# module.net
KiCad netlist of a schematic drawn in Altium Designer
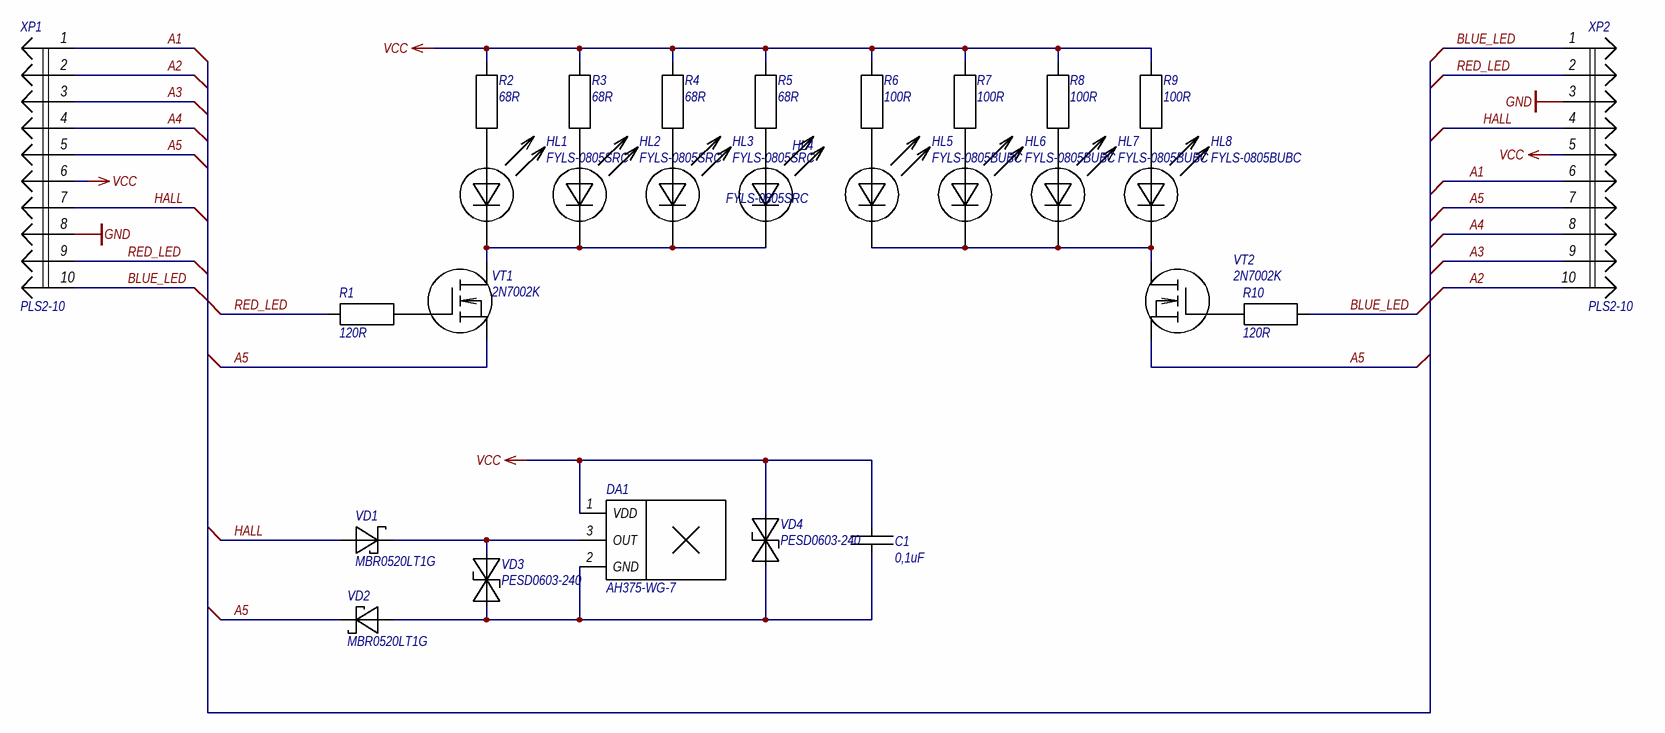
[diagram p0: module.SchDoc]

(export (version "E")
  (design (tool "Eeschema 10.0.6"))
  (components
    (comp (ref "C1")
      (value "0,1uF")
      (footprint "C0805C")
      (description "CC0805KKX7R0BB104, 0805 X7R  0,1 uF 100V")
      (fields (field (name "PART NUMBER") "CC0805KKX7R0BB104") (field (name "MANUFACTURER") "Yageo"))
      (libsource (lib "lib") (part "Cap"))
    )
    (comp (ref "DA1")
      (value "AH375-WG-7")
      (footprint "SOT23-3(1-3-2)")
      (description "SINGLE PHASE HALL EFFECT LATCH")
      (fields (field (name "MANUFACTURER") "Diodes Incorporated"))
      (libsource (lib "lib") (part "AH375"))
    )
    (comp (ref "HL1")
      (value "FYLS-0805SRC")
      (footprint "LED0805")
      (description "SMD 0805 Red 20mA 15mcd")
      (fields (field (name "MANUFACTURER") "Foryard") (field (name "VOLTAGE") "1,7V"))
      (libsource (lib "lib") (part "LED"))
    )
    (comp (ref "HL2")
      (value "FYLS-0805SRC")
      (footprint "LED0805")
      (description "SMD 0805 Red 20mA 15mcd")
      (fields (field (name "MANUFACTURER") "Foryard") (field (name "VOLTAGE") "1,7V"))
      (libsource (lib "lib") (part "LED"))
    )
    (comp (ref "HL3")
      (value "FYLS-0805SRC")
      (footprint "LED0805")
      (description "SMD 0805 Red 20mA 15mcd")
      (fields (field (name "MANUFACTURER") "Foryard") (field (name "VOLTAGE") "1,7V"))
      (libsource (lib "lib") (part "LED"))
    )
    (comp (ref "HL4")
      (value "FYLS-0805SRC")
      (footprint "LED0805")
      (description "SMD 0805 Red 20mA 15mcd")
      (fields (field (name "MANUFACTURER") "Foryard") (field (name "VOLTAGE") "1,7V"))
      (libsource (lib "lib") (part "LED"))
    )
    (comp (ref "HL5")
      (value "FYLS-0805BUBC")
      (footprint "LED0805")
      (description "SMD 0805 Blue 20mA 120mcd")
      (fields (field (name "MANUFACTURER") "Foryard") (field (name "VOLTAGE") "3.2V"))
      (libsource (lib "lib") (part "LED"))
    )
    (comp (ref "HL6")
      (value "FYLS-0805BUBC")
      (footprint "LED0805")
      (description "SMD 0805 Blue 20mA 120mcd")
      (fields (field (name "MANUFACTURER") "Foryard") (field (name "VOLTAGE") "3.2V"))
      (libsource (lib "lib") (part "LED"))
    )
    (comp (ref "HL7")
      (value "FYLS-0805BUBC")
      (footprint "LED0805")
      (description "SMD 0805 Blue 20mA 120mcd")
      (fields (field (name "MANUFACTURER") "Foryard") (field (name "VOLTAGE") "3.2V"))
      (libsource (lib "lib") (part "LED"))
    )
    (comp (ref "HL8")
      (value "FYLS-0805BUBC")
      (footprint "LED0805")
      (description "SMD 0805 Blue 20mA 120mcd")
      (fields (field (name "MANUFACTURER") "Foryard") (field (name "VOLTAGE") "3.2V"))
      (libsource (lib "lib") (part "LED"))
    )
    (comp (ref "R1")
      (value "120R")
      (footprint "C0603R")
      (description "RC0603FR-07120RL, 1% 120R")
      (fields (field (name "PART NUMBER") "RC0603FR-07120RL") (field (name "MANUFACTURER") "Yageo"))
      (libsource (lib "lib") (part "res"))
    )
    (comp (ref "R2")
      (value "68R")
      (footprint "C0805R")
      (description "RC0805FR-0768RL, 1% 68R")
      (fields (field (name "PART NUMBER") "RC0805FR-0768RL") (field (name "MANUFACTURER") "Yageo"))
      (libsource (lib "lib") (part "res"))
    )
    (comp (ref "R3")
      (value "68R")
      (footprint "C0805R")
      (description "RC0805FR-0768RL, 1% 68R")
      (fields (field (name "PART NUMBER") "RC0805FR-0768RL") (field (name "MANUFACTURER") "Yageo"))
      (libsource (lib "lib") (part "res"))
    )
    (comp (ref "R4")
      (value "68R")
      (footprint "C0805R")
      (description "RC0805FR-0768RL, 1% 68R")
      (fields (field (name "PART NUMBER") "RC0805FR-0768RL") (field (name "MANUFACTURER") "Yageo"))
      (libsource (lib "lib") (part "res"))
    )
    (comp (ref "R5")
      (value "68R")
      (footprint "C0805R")
      (description "RC0805FR-0768RL, 1% 68R")
      (fields (field (name "PART NUMBER") "RC0805FR-0768RL") (field (name "MANUFACTURER") "Yageo"))
      (libsource (lib "lib") (part "res"))
    )
    (comp (ref "R6")
      (value "100R")
      (footprint "C0805R")
      (description "RC0805FR-07100RL, 1% 100R")
      (fields (field (name "PART NUMBER") "RC0805FR-07100RL") (field (name "MANUFACTURER") "Yageo"))
      (libsource (lib "lib") (part "res"))
    )
    (comp (ref "R7")
      (value "100R")
      (footprint "C0805R")
      (description "RC0805FR-07100RL, 1% 100R")
      (fields (field (name "PART NUMBER") "RC0805FR-07100RL") (field (name "MANUFACTURER") "Yageo"))
      (libsource (lib "lib") (part "res"))
    )
    (comp (ref "R8")
      (value "100R")
      (footprint "C0805R")
      (description "RC0805FR-07100RL, 1% 100R")
      (fields (field (name "PART NUMBER") "RC0805FR-07100RL") (field (name "MANUFACTURER") "Yageo"))
      (libsource (lib "lib") (part "res"))
    )
    (comp (ref "R9")
      (value "100R")
      (footprint "C0805R")
      (description "RC0805FR-07100RL, 1% 100R")
      (fields (field (name "PART NUMBER") "RC0805FR-07100RL") (field (name "MANUFACTURER") "Yageo"))
      (libsource (lib "lib") (part "res"))
    )
    (comp (ref "R10")
      (value "120R")
      (footprint "C0603R")
      (description "RC0603FR-07120RL, 1% 120R")
      (fields (field (name "PART NUMBER") "RC0603FR-07120RL") (field (name "MANUFACTURER") "Yageo"))
      (libsource (lib "lib") (part "res"))
    )
    (comp (ref "VD1")
      (value "MBR0520LT1G")
      (footprint "SOD123")
      (description "MBR0520LT1G, SOD123 V A, V")
      (libsource (lib "lib") (part "Schottky"))
    )
    (comp (ref "VD2")
      (value "MBR0520LT1G")
      (footprint "SOD123")
      (description "MBR0520LT1G, SOD123 V A, V")
      (libsource (lib "lib") (part "Schottky"))
    )
    (comp (ref "VD3")
      (value "PESD0603-240")
      (footprint "C0603D")
      (description "PESD0603-240, SMD 0603 24V   BI-directional")
      (fields (field (name "MANUFACTURER") "Littelfuse, Inc") (field (name "VOLTAGE") "24"))
      (libsource (lib "lib") (part "ZENER2A"))
    )
    (comp (ref "VD4")
      (value "PESD0603-240")
      (footprint "C0603D")
      (description "PESD0603-240, SMD 0603 24V   BI-directional")
      (fields (field (name "MANUFACTURER") "Littelfuse, Inc") (field (name "VOLTAGE") "24"))
      (libsource (lib "lib") (part "ZENER2A"))
    )
    (comp (ref "VT1")
      (value "2N7002K")
      (footprint "SOT23-3-FET")
      (description "2N7002K, SOT23-3 0,3A 60V")
      (fields (field (name "MANUFACTURER") "ON semiconductor"))
      (libsource (lib "lib") (part "TRANS-N-FET"))
    )
    (comp (ref "VT2")
      (value "2N7002K")
      (footprint "SOT23-3-FET")
      (description "2N7002K, SOT23-3 0,3A 60V")
      (fields (field (name "MANUFACTURER") "ON semiconductor"))
      (libsource (lib "lib") (part "TRANS-N-FET"))
    )
    (comp (ref "XP1")
      (value "PLS2-10")
      (footprint "PLS2-10")
      (description "PLS2-10, ,  10 Pins")
      (libsource (lib "lib") (part "Connector-10"))
    )
    (comp (ref "XP2")
      (value "PLS2-10")
      (footprint "PLS2-10")
      (description "PLS2-10, ,  10 Pins")
      (libsource (lib "lib") (part "Connector-10"))
    )
  )
  (nets
    (net (code "1") (name "/A1") (class "Default")
      (node (ref "XP1") (pin "1") (pinfunction "1_1") (pintype "passive"))
      (node (ref "XP2") (pin "6") (pinfunction "6_6") (pintype "passive"))
    )
    (net (code "2") (name "/A2") (class "Default")
      (node (ref "XP1") (pin "2") (pinfunction "2_2") (pintype "passive"))
      (node (ref "XP2") (pin "10") (pinfunction "10_10") (pintype "passive"))
    )
    (net (code "3") (name "/A3") (class "Default")
      (node (ref "XP1") (pin "3") (pinfunction "3_3") (pintype "passive"))
      (node (ref "XP2") (pin "9") (pinfunction "9_9") (pintype "passive"))
    )
    (net (code "4") (name "/A4") (class "Default")
      (node (ref "XP1") (pin "4") (pinfunction "4_4") (pintype "passive"))
      (node (ref "XP2") (pin "8") (pinfunction "8_8") (pintype "passive"))
    )
    (net (code "5") (name "/A5") (class "Default")
      (node (ref "VD2") (pin "C") (pinfunction "C_C") (pintype "passive"))
      (node (ref "VT1") (pin "S") (pinfunction "S_S") (pintype "passive"))
      (node (ref "VT2") (pin "S") (pinfunction "S_S") (pintype "passive"))
      (node (ref "XP1") (pin "5") (pinfunction "5_5") (pintype "passive"))
      (node (ref "XP2") (pin "7") (pinfunction "7_7") (pintype "passive"))
    )
    (net (code "6") (name "/BLUE_LED") (class "Default")
      (node (ref "R10") (pin "1") (pinfunction "1_1") (pintype "passive"))
      (node (ref "XP1") (pin "10") (pinfunction "10_10") (pintype "passive"))
      (node (ref "XP2") (pin "1") (pinfunction "1_1") (pintype "passive"))
    )
    (net (code "7") (name "/HALL") (class "Default")
      (node (ref "VD1") (pin "A") (pinfunction "A_A") (pintype "passive"))
      (node (ref "XP1") (pin "7") (pinfunction "7_7") (pintype "passive"))
      (node (ref "XP2") (pin "4") (pinfunction "4_4") (pintype "passive"))
    )
    (net (code "8") (name "/RED_LED") (class "Default")
      (node (ref "R1") (pin "1") (pinfunction "1_1") (pintype "passive"))
      (node (ref "XP1") (pin "9") (pinfunction "9_9") (pintype "passive"))
      (node (ref "XP2") (pin "2") (pinfunction "2_2") (pintype "passive"))
    )
    (net (code "9") (name "GND") (class "Default")
      (node (ref "XP1") (pin "8") (pinfunction "8_8") (pintype "passive"))
      (node (ref "XP2") (pin "3") (pinfunction "3_3") (pintype "passive"))
    )
    (net (code "10") (name "Net-(DA1-GND)") (class "Default")
      (node (ref "C1") (pin "2") (pinfunction "2_2") (pintype "passive"))
      (node (ref "DA1") (pin "2") (pinfunction "GND_2") (pintype "passive"))
      (node (ref "VD2") (pin "A") (pinfunction "A_A") (pintype "passive"))
      (node (ref "VD3") (pin "A") (pinfunction "A_A") (pintype "passive"))
      (node (ref "VD4") (pin "A") (pinfunction "A_A") (pintype "passive"))
    )
    (net (code "11") (name "Net-(DA1-OUT)") (class "Default")
      (node (ref "DA1") (pin "3") (pinfunction "OUT_3") (pintype "passive"))
      (node (ref "VD1") (pin "C") (pinfunction "C_C") (pintype "passive"))
      (node (ref "VD3") (pin "C") (pinfunction "C_C") (pintype "passive"))
    )
    (net (code "12") (name "Net-(HL1-A)") (class "Default")
      (node (ref "HL1") (pin "1") (pinfunction "A_1") (pintype "passive"))
      (node (ref "R2") (pin "2") (pinfunction "2_2") (pintype "passive"))
    )
    (net (code "13") (name "Net-(HL1-C)") (class "Default")
      (node (ref "HL1") (pin "2") (pinfunction "C_2") (pintype "passive"))
      (node (ref "HL2") (pin "2") (pinfunction "C_2") (pintype "passive"))
      (node (ref "HL3") (pin "2") (pinfunction "C_2") (pintype "passive"))
      (node (ref "HL4") (pin "2") (pinfunction "C_2") (pintype "passive"))
      (node (ref "VT1") (pin "D") (pinfunction "D_D") (pintype "passive"))
    )
    (net (code "14") (name "Net-(HL2-A)") (class "Default")
      (node (ref "HL2") (pin "1") (pinfunction "A_1") (pintype "passive"))
      (node (ref "R3") (pin "2") (pinfunction "2_2") (pintype "passive"))
    )
    (net (code "15") (name "Net-(HL3-A)") (class "Default")
      (node (ref "HL3") (pin "1") (pinfunction "A_1") (pintype "passive"))
      (node (ref "R4") (pin "2") (pinfunction "2_2") (pintype "passive"))
    )
    (net (code "16") (name "Net-(HL4-A)") (class "Default")
      (node (ref "HL4") (pin "1") (pinfunction "A_1") (pintype "passive"))
      (node (ref "R5") (pin "2") (pinfunction "2_2") (pintype "passive"))
    )
    (net (code "17") (name "Net-(HL5-A)") (class "Default")
      (node (ref "HL5") (pin "1") (pinfunction "A_1") (pintype "passive"))
      (node (ref "R6") (pin "2") (pinfunction "2_2") (pintype "passive"))
    )
    (net (code "18") (name "Net-(HL5-C)") (class "Default")
      (node (ref "HL5") (pin "2") (pinfunction "C_2") (pintype "passive"))
      (node (ref "HL6") (pin "2") (pinfunction "C_2") (pintype "passive"))
      (node (ref "HL7") (pin "2") (pinfunction "C_2") (pintype "passive"))
      (node (ref "HL8") (pin "2") (pinfunction "C_2") (pintype "passive"))
      (node (ref "VT2") (pin "D") (pinfunction "D_D") (pintype "passive"))
    )
    (net (code "19") (name "Net-(HL6-A)") (class "Default")
      (node (ref "HL6") (pin "1") (pinfunction "A_1") (pintype "passive"))
      (node (ref "R7") (pin "2") (pinfunction "2_2") (pintype "passive"))
    )
    (net (code "20") (name "Net-(HL7-A)") (class "Default")
      (node (ref "HL7") (pin "1") (pinfunction "A_1") (pintype "passive"))
      (node (ref "R8") (pin "2") (pinfunction "2_2") (pintype "passive"))
    )
    (net (code "21") (name "Net-(HL8-A)") (class "Default")
      (node (ref "HL8") (pin "1") (pinfunction "A_1") (pintype "passive"))
      (node (ref "R9") (pin "2") (pinfunction "2_2") (pintype "passive"))
    )
    (net (code "22") (name "Net-(R1-Pad2)") (class "Default")
      (node (ref "R1") (pin "2") (pinfunction "2_2") (pintype "passive"))
      (node (ref "VT1") (pin "G") (pinfunction "G_G") (pintype "passive"))
    )
    (net (code "23") (name "Net-(R10-Pad2)") (class "Default")
      (node (ref "R10") (pin "2") (pinfunction "2_2") (pintype "passive"))
      (node (ref "VT2") (pin "G") (pinfunction "G_G") (pintype "passive"))
    )
    (net (code "24") (name "VCC") (class "Default")
      (node (ref "C1") (pin "1") (pinfunction "1_1") (pintype "passive"))
      (node (ref "DA1") (pin "1") (pinfunction "VDD_1") (pintype "passive"))
      (node (ref "R2") (pin "1") (pinfunction "1_1") (pintype "passive"))
      (node (ref "R3") (pin "1") (pinfunction "1_1") (pintype "passive"))
      (node (ref "R4") (pin "1") (pinfunction "1_1") (pintype "passive"))
      (node (ref "R5") (pin "1") (pinfunction "1_1") (pintype "passive"))
      (node (ref "R6") (pin "1") (pinfunction "1_1") (pintype "passive"))
      (node (ref "R7") (pin "1") (pinfunction "1_1") (pintype "passive"))
      (node (ref "R8") (pin "1") (pinfunction "1_1") (pintype "passive"))
      (node (ref "R9") (pin "1") (pinfunction "1_1") (pintype "passive"))
      (node (ref "VD4") (pin "C") (pinfunction "C_C") (pintype "passive"))
      (node (ref "XP1") (pin "6") (pinfunction "6_6") (pintype "passive"))
      (node (ref "XP2") (pin "5") (pinfunction "5_5") (pintype "passive"))
    )
  )
)
